# Platine_Messgeraet_Frank_20220825-v003.net
KiCad netlist of a schematic drawn in EAGLE
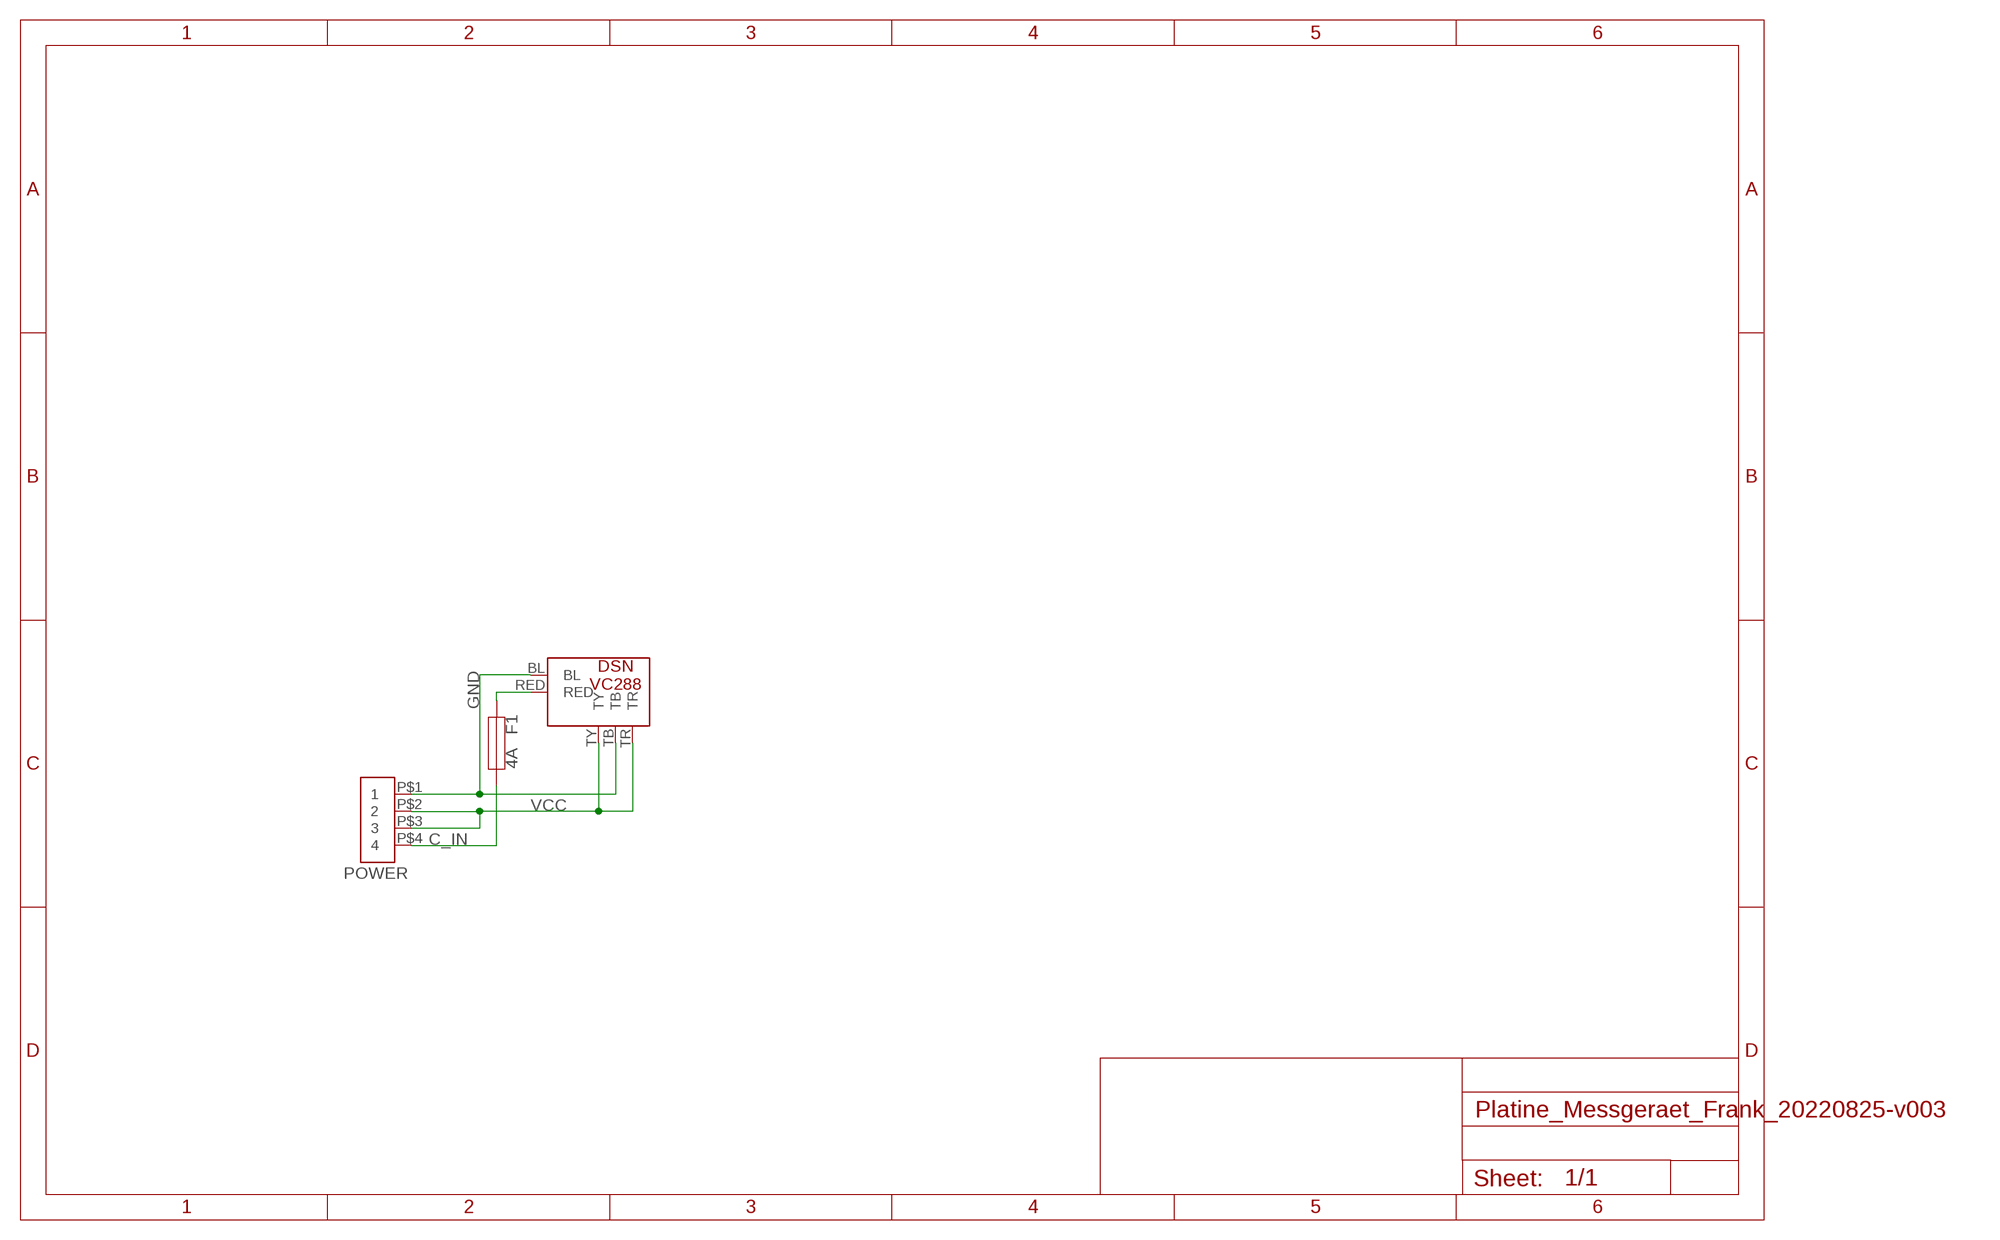
[diagram p0: schematic, sheet 1]

(export (version "E")
  (design (tool "Eeschema 10.0.6"))
  (components
    (comp (ref "F1")
      (value "4A")
      (footprint "eagle-import:FUSE_5X20-L")
      (libsource (lib "eagle-import") (part "FUSES90"))
    )
    (comp (ref "POWER")
      (value "CB-SCREW-4P0°")
      (footprint "eagle-import:CTB932VD-4")
      (libsource (lib "eagle-import") (part "CB-SCREW-4P0°"))
    )
    (comp (ref "U$1")
      (value "DSN-VC288")
      (footprint "eagle-import:DSN-VC288")
      (libsource (lib "eagle-import") (part "DSN-VC288"))
    )
  )
  (nets
    (net (code "1") (name "/C_IN") (class "Default")
      (node (ref "F1") (pin "1") (pinfunction "1_1") (pintype "bidirectional"))
      (node (ref "POWER") (pin "P$4") (pinfunction "4_P$4") (pintype "bidirectional"))
    )
    (net (code "2") (name "/GND") (class "Default")
      (node (ref "POWER") (pin "P$1") (pinfunction "1_P$1") (pintype "bidirectional"))
      (node (ref "U$1") (pin "BL") (pinfunction "BL_BL") (pintype "bidirectional"))
      (node (ref "U$1") (pin "TB") (pinfunction "TB_TB") (pintype "bidirectional"))
    )
    (net (code "3") (name "/VCC") (class "Default")
      (node (ref "POWER") (pin "P$2") (pinfunction "2_P$2") (pintype "bidirectional"))
      (node (ref "POWER") (pin "P$3") (pinfunction "3_P$3") (pintype "bidirectional"))
      (node (ref "U$1") (pin "TR") (pinfunction "TR_TR") (pintype "bidirectional"))
      (node (ref "U$1") (pin "TY") (pinfunction "TY_TY") (pintype "bidirectional"))
    )
    (net (code "4") (name "Net-(F1-Pad2)") (class "Default")
      (node (ref "F1") (pin "2") (pinfunction "2_2") (pintype "bidirectional"))
      (node (ref "U$1") (pin "RED") (pinfunction "RED_RED") (pintype "bidirectional"))
    )
  )
)
